# a210-4-band-eq.net
KiCad netlist of a schematic drawn in EAGLE
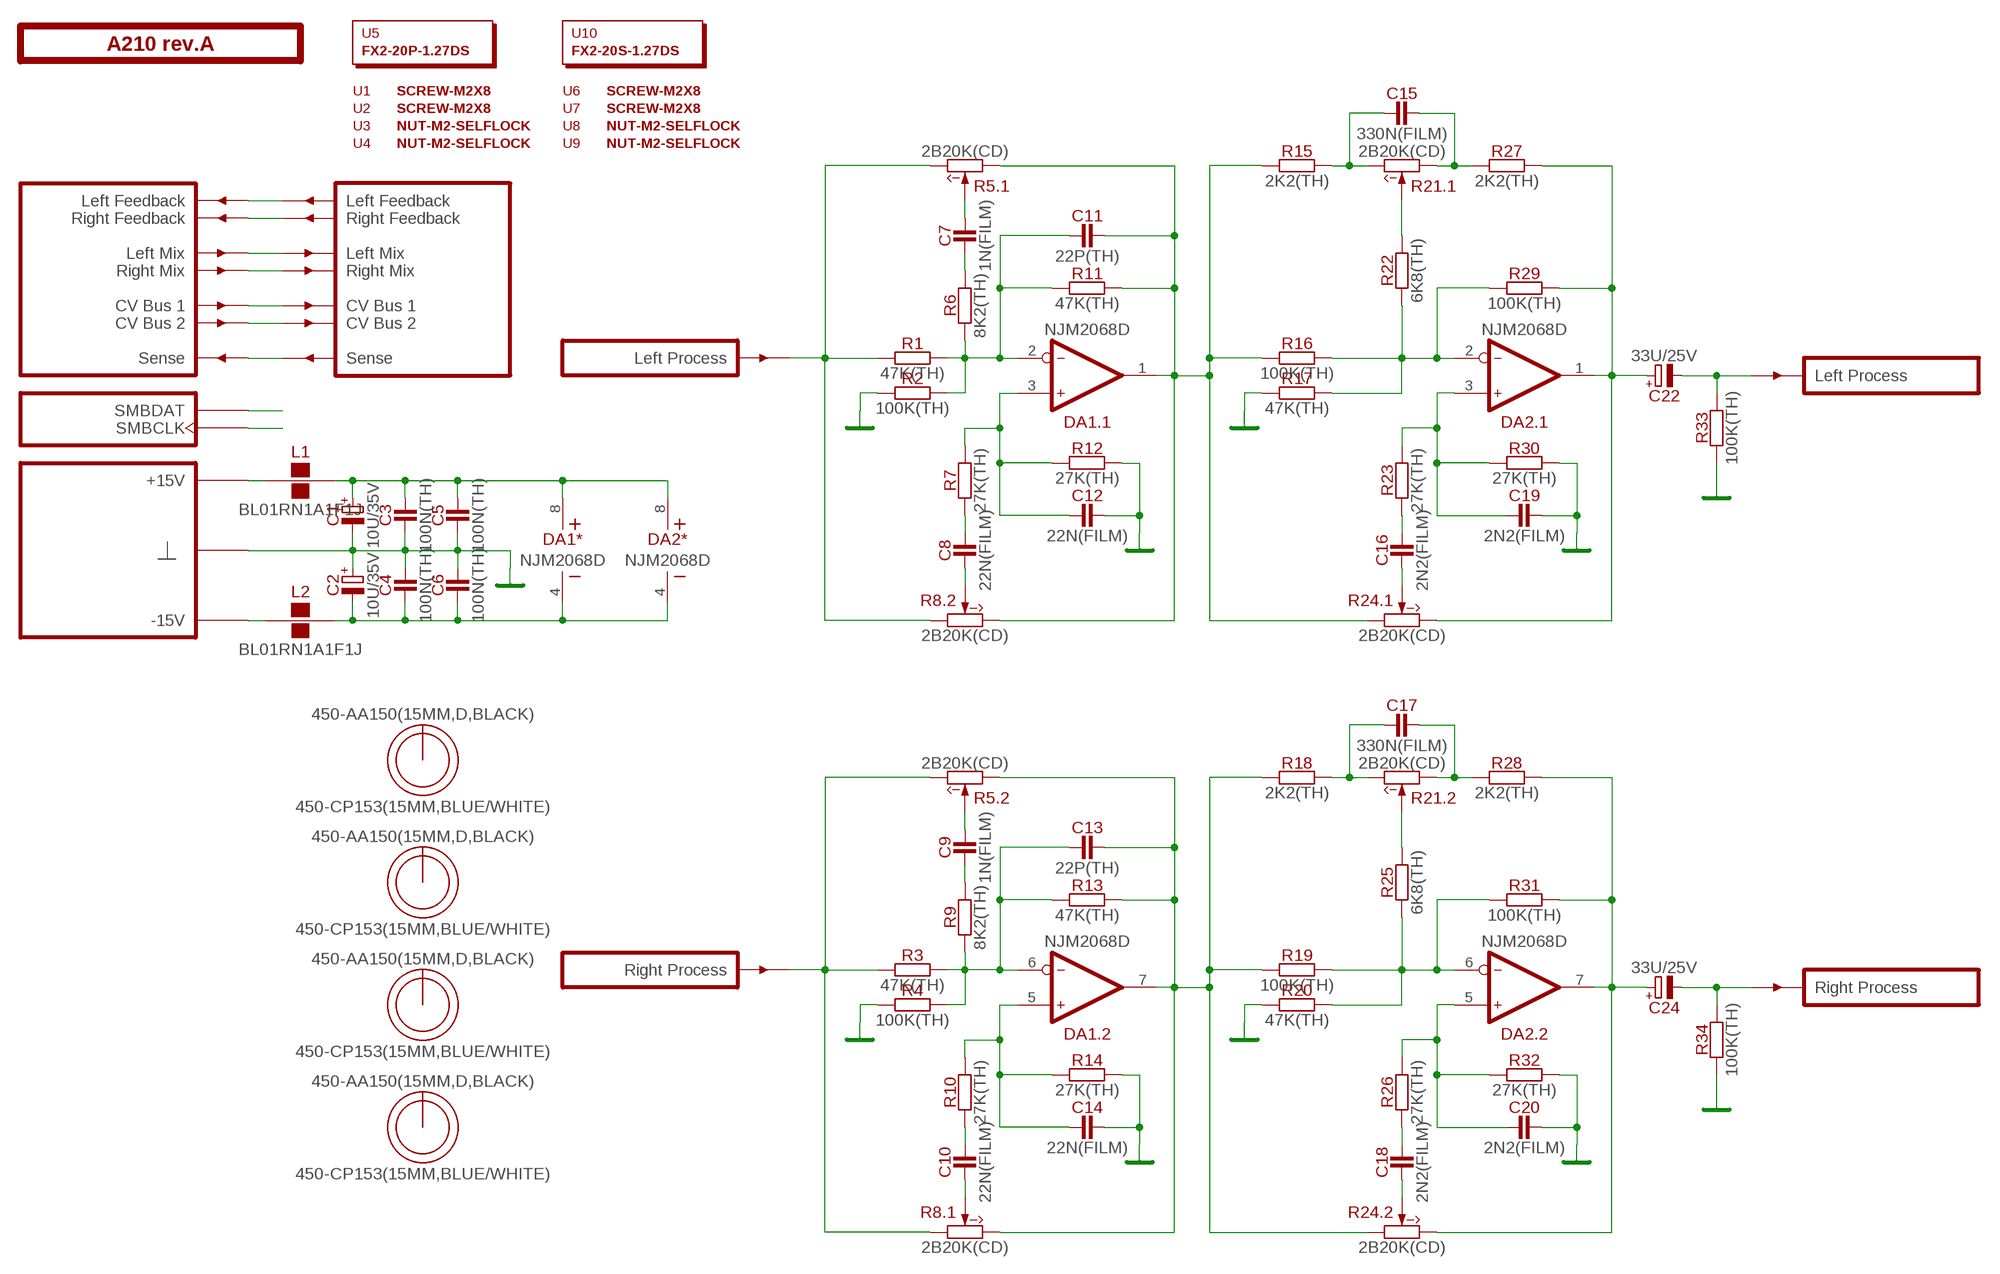
[diagram p0: schematic, sheet 1]

(export (version "E")
  (design (tool "Eeschema 10.0.6"))
  (components
    (comp (ref "C1")
      (value "10U/35V")
      (footprint "eagle-import:E2-5")
      (libsource (lib "eagle-import") (part "?10U/35V"))
    )
    (comp (ref "C2")
      (value "10U/35V")
      (footprint "eagle-import:E2-5")
      (libsource (lib "eagle-import") (part "?10U/35V"))
    )
    (comp (ref "C3")
      (value "100N(TH)")
      (footprint "eagle-import:C050-024X044")
      (libsource (lib "eagle-import") (part "?100N(TH)"))
    )
    (comp (ref "C4")
      (value "100N(TH)")
      (footprint "eagle-import:C050-024X044")
      (libsource (lib "eagle-import") (part "?100N(TH)"))
    )
    (comp (ref "C5")
      (value "100N(TH)")
      (footprint "eagle-import:C050-024X044")
      (libsource (lib "eagle-import") (part "?100N(TH)"))
    )
    (comp (ref "C6")
      (value "100N(TH)")
      (footprint "eagle-import:C050-024X044")
      (libsource (lib "eagle-import") (part "?100N(TH)"))
    )
    (comp (ref "C7")
      (value "1N(FILM)")
      (footprint "eagle-import:C050-025X075")
      (libsource (lib "eagle-import") (part "?1N(FILM)"))
    )
    (comp (ref "C8")
      (value "22N(FILM)")
      (footprint "eagle-import:C050-025X075")
      (libsource (lib "eagle-import") (part "?22N(FILM)"))
    )
    (comp (ref "C9")
      (value "1N(FILM)")
      (footprint "eagle-import:C050-025X075")
      (libsource (lib "eagle-import") (part "?1N(FILM)"))
    )
    (comp (ref "C10")
      (value "22N(FILM)")
      (footprint "eagle-import:C050-025X075")
      (libsource (lib "eagle-import") (part "?22N(FILM)"))
    )
    (comp (ref "C11")
      (value "22P(TH)")
      (footprint "eagle-import:C050-024X044")
      (libsource (lib "eagle-import") (part "?22P(TH)"))
    )
    (comp (ref "C12")
      (value "22N(FILM)")
      (footprint "eagle-import:C050-025X075")
      (libsource (lib "eagle-import") (part "?22N(FILM)"))
    )
    (comp (ref "C13")
      (value "22P(TH)")
      (footprint "eagle-import:C050-024X044")
      (libsource (lib "eagle-import") (part "?22P(TH)"))
    )
    (comp (ref "C14")
      (value "22N(FILM)")
      (footprint "eagle-import:C050-025X075")
      (libsource (lib "eagle-import") (part "?22N(FILM)"))
    )
    (comp (ref "C15")
      (value "330N(FILM)")
      (footprint "eagle-import:C050-035X075")
      (libsource (lib "eagle-import") (part "?330N(FILM)"))
    )
    (comp (ref "C16")
      (value "2N2(FILM)")
      (footprint "eagle-import:C050-025X075")
      (libsource (lib "eagle-import") (part "?2N2(FILM)"))
    )
    (comp (ref "C17")
      (value "330N(FILM)")
      (footprint "eagle-import:C050-035X075")
      (libsource (lib "eagle-import") (part "?330N(FILM)"))
    )
    (comp (ref "C18")
      (value "2N2(FILM)")
      (footprint "eagle-import:C050-025X075")
      (libsource (lib "eagle-import") (part "?2N2(FILM)"))
    )
    (comp (ref "C19")
      (value "2N2(FILM)")
      (footprint "eagle-import:C050-025X075")
      (libsource (lib "eagle-import") (part "?2N2(FILM)"))
    )
    (comp (ref "C20")
      (value "2N2(FILM)")
      (footprint "eagle-import:C050-025X075")
      (libsource (lib "eagle-import") (part "?2N2(FILM)"))
    )
    (comp (ref "C22")
      (value "33U/25V")
      (footprint "eagle-import:E2,5-7")
      (libsource (lib "eagle-import") (part "?33U/25V"))
    )
    (comp (ref "C24")
      (value "33U/25V")
      (footprint "eagle-import:E2,5-7")
      (libsource (lib "eagle-import") (part "?33U/25V"))
    )
    (comp (ref "DA1")
      (value "NJM2068D")
      (footprint "eagle-import:DIP-8")
      (libsource (lib "eagle-import") (part "NJM2068D"))
    )
    (comp (ref "DA2")
      (value "NJM2068D")
      (footprint "eagle-import:DIP-8")
      (libsource (lib "eagle-import") (part "NJM2068D"))
    )
    (comp (ref "L1")
      (value "BL01RN1A1F1J")
      (footprint "eagle-import:BL01RN1A")
      (libsource (lib "eagle-import") (part "BL01RN1A?1F1J"))
    )
    (comp (ref "L2")
      (value "BL01RN1A1F1J")
      (footprint "eagle-import:BL01RN1A")
      (libsource (lib "eagle-import") (part "BL01RN1A?1F1J"))
    )
    (comp (ref "O1")
      (value "450-AA150(15MM,D,BLACK)")
      (footprint "eagle-import:EMPTY")
      (libsource (lib "eagle-import") (part "450-AA?150(15MM,D,BLACK)"))
    )
    (comp (ref "O2")
      (value "450-AA150(15MM,D,BLACK)")
      (footprint "eagle-import:EMPTY")
      (libsource (lib "eagle-import") (part "450-AA?150(15MM,D,BLACK)"))
    )
    (comp (ref "O3")
      (value "450-AA150(15MM,D,BLACK)")
      (footprint "eagle-import:EMPTY")
      (libsource (lib "eagle-import") (part "450-AA?150(15MM,D,BLACK)"))
    )
    (comp (ref "O4")
      (value "450-AA150(15MM,D,BLACK)")
      (footprint "eagle-import:EMPTY")
      (libsource (lib "eagle-import") (part "450-AA?150(15MM,D,BLACK)"))
    )
    (comp (ref "O5")
      (value "450-CP153(15MM,BLUE/WHITE)")
      (footprint "eagle-import:EMPTY")
      (libsource (lib "eagle-import") (part "450-C?P153(15MM,BLUE/WHITE)"))
    )
    (comp (ref "O6")
      (value "450-CP153(15MM,BLUE/WHITE)")
      (footprint "eagle-import:EMPTY")
      (libsource (lib "eagle-import") (part "450-C?P153(15MM,BLUE/WHITE)"))
    )
    (comp (ref "O7")
      (value "450-CP153(15MM,BLUE/WHITE)")
      (footprint "eagle-import:EMPTY")
      (libsource (lib "eagle-import") (part "450-C?P153(15MM,BLUE/WHITE)"))
    )
    (comp (ref "O8")
      (value "450-CP153(15MM,BLUE/WHITE)")
      (footprint "eagle-import:EMPTY")
      (libsource (lib "eagle-import") (part "450-C?P153(15MM,BLUE/WHITE)"))
    )
    (comp (ref "PCB1")
      (value "A210 rev.A")
      (footprint "eagle-import:ST2-BOARD-50")
      (libsource (lib "eagle-import") (part "ST2-BOARD-?50"))
    )
    (comp (ref "R1")
      (value "47K(TH)")
      (footprint "eagle-import:R-0207_10")
      (libsource (lib "eagle-import") (part "?47K(TH)"))
    )
    (comp (ref "R2")
      (value "100K(TH)")
      (footprint "eagle-import:R-0207_10")
      (libsource (lib "eagle-import") (part "?100K(TH)"))
    )
    (comp (ref "R3")
      (value "47K(TH)")
      (footprint "eagle-import:R-0207_10")
      (libsource (lib "eagle-import") (part "?47K(TH)"))
    )
    (comp (ref "R4")
      (value "100K(TH)")
      (footprint "eagle-import:R-0207_10")
      (libsource (lib "eagle-import") (part "?100K(TH)"))
    )
    (comp (ref "R5")
      (value "2B20K(CD)")
      (footprint "eagle-import:RV11-DUAL")
      (libsource (lib "eagle-import") (part "2?B20K(CD)"))
    )
    (comp (ref "R6")
      (value "8K2(TH)")
      (footprint "eagle-import:R-0207_10")
      (libsource (lib "eagle-import") (part "?8K2(TH)"))
    )
    (comp (ref "R7")
      (value "27K(TH)")
      (footprint "eagle-import:R-0207_10")
      (libsource (lib "eagle-import") (part "?27K(TH)"))
    )
    (comp (ref "R8")
      (value "2B20K(CD)")
      (footprint "eagle-import:RV11-DUAL")
      (libsource (lib "eagle-import") (part "2?B20K(CD)"))
    )
    (comp (ref "R9")
      (value "8K2(TH)")
      (footprint "eagle-import:R-0207_10")
      (libsource (lib "eagle-import") (part "?8K2(TH)"))
    )
    (comp (ref "R10")
      (value "27K(TH)")
      (footprint "eagle-import:R-0207_10")
      (libsource (lib "eagle-import") (part "?27K(TH)"))
    )
    (comp (ref "R11")
      (value "47K(TH)")
      (footprint "eagle-import:R-0207_10")
      (libsource (lib "eagle-import") (part "?47K(TH)"))
    )
    (comp (ref "R12")
      (value "27K(TH)")
      (footprint "eagle-import:R-0207_10")
      (libsource (lib "eagle-import") (part "?27K(TH)"))
    )
    (comp (ref "R13")
      (value "47K(TH)")
      (footprint "eagle-import:R-0207_10")
      (libsource (lib "eagle-import") (part "?47K(TH)"))
    )
    (comp (ref "R14")
      (value "27K(TH)")
      (footprint "eagle-import:R-0207_10")
      (libsource (lib "eagle-import") (part "?27K(TH)"))
    )
    (comp (ref "R15")
      (value "2K2(TH)")
      (footprint "eagle-import:R-0207_10")
      (libsource (lib "eagle-import") (part "?2K2(TH)"))
    )
    (comp (ref "R16")
      (value "100K(TH)")
      (footprint "eagle-import:R-0207_10")
      (libsource (lib "eagle-import") (part "?100K(TH)"))
    )
    (comp (ref "R17")
      (value "47K(TH)")
      (footprint "eagle-import:R-0207_10")
      (libsource (lib "eagle-import") (part "?47K(TH)"))
    )
    (comp (ref "R18")
      (value "2K2(TH)")
      (footprint "eagle-import:R-0207_10")
      (libsource (lib "eagle-import") (part "?2K2(TH)"))
    )
    (comp (ref "R19")
      (value "100K(TH)")
      (footprint "eagle-import:R-0207_10")
      (libsource (lib "eagle-import") (part "?100K(TH)"))
    )
    (comp (ref "R20")
      (value "47K(TH)")
      (footprint "eagle-import:R-0207_10")
      (libsource (lib "eagle-import") (part "?47K(TH)"))
    )
    (comp (ref "R21")
      (value "2B20K(CD)")
      (footprint "eagle-import:RV11-DUAL")
      (libsource (lib "eagle-import") (part "2?B20K(CD)"))
    )
    (comp (ref "R22")
      (value "6K8(TH)")
      (footprint "eagle-import:R-0207_10")
      (libsource (lib "eagle-import") (part "?6K8(TH)"))
    )
    (comp (ref "R23")
      (value "27K(TH)")
      (footprint "eagle-import:R-0207_10")
      (libsource (lib "eagle-import") (part "?27K(TH)"))
    )
    (comp (ref "R24")
      (value "2B20K(CD)")
      (footprint "eagle-import:RV11-DUAL")
      (libsource (lib "eagle-import") (part "2?B20K(CD)"))
    )
    (comp (ref "R25")
      (value "6K8(TH)")
      (footprint "eagle-import:R-0207_10")
      (libsource (lib "eagle-import") (part "?6K8(TH)"))
    )
    (comp (ref "R26")
      (value "27K(TH)")
      (footprint "eagle-import:R-0207_10")
      (libsource (lib "eagle-import") (part "?27K(TH)"))
    )
    (comp (ref "R27")
      (value "2K2(TH)")
      (footprint "eagle-import:R-0207_10")
      (libsource (lib "eagle-import") (part "?2K2(TH)"))
    )
    (comp (ref "R28")
      (value "2K2(TH)")
      (footprint "eagle-import:R-0207_10")
      (libsource (lib "eagle-import") (part "?2K2(TH)"))
    )
    (comp (ref "R29")
      (value "100K(TH)")
      (footprint "eagle-import:R-0207_10")
      (libsource (lib "eagle-import") (part "?100K(TH)"))
    )
    (comp (ref "R30")
      (value "27K(TH)")
      (footprint "eagle-import:R-0207_10")
      (libsource (lib "eagle-import") (part "?27K(TH)"))
    )
    (comp (ref "R31")
      (value "100K(TH)")
      (footprint "eagle-import:R-0207_10")
      (libsource (lib "eagle-import") (part "?100K(TH)"))
    )
    (comp (ref "R32")
      (value "27K(TH)")
      (footprint "eagle-import:R-0207_10")
      (libsource (lib "eagle-import") (part "?27K(TH)"))
    )
    (comp (ref "R33")
      (value "100K(TH)")
      (footprint "eagle-import:R-0207_10")
      (libsource (lib "eagle-import") (part "?100K(TH)"))
    )
    (comp (ref "R34")
      (value "100K(TH)")
      (footprint "eagle-import:R-0207_10")
      (libsource (lib "eagle-import") (part "?100K(TH)"))
    )
    (comp (ref "U1")
      (value "SCREW-M2X8")
      (footprint "eagle-import:EMPTY")
      (libsource (lib "eagle-import") (part "?SCREW-M2X8"))
    )
    (comp (ref "U2")
      (value "SCREW-M2X8")
      (footprint "eagle-import:EMPTY")
      (libsource (lib "eagle-import") (part "?SCREW-M2X8"))
    )
    (comp (ref "U3")
      (value "NUT-M2-SELFLOCK")
      (footprint "eagle-import:EMPTY")
      (libsource (lib "eagle-import") (part "?NUT-M2-SELFLOCK"))
    )
    (comp (ref "U4")
      (value "NUT-M2-SELFLOCK")
      (footprint "eagle-import:EMPTY")
      (libsource (lib "eagle-import") (part "?NUT-M2-SELFLOCK"))
    )
    (comp (ref "U5")
      (value "FX2-20P-1.27DS")
      (footprint "eagle-import:EMPTY")
      (libsource (lib "eagle-import") (part "?FX2-20P-1.27DS"))
    )
    (comp (ref "U6")
      (value "SCREW-M2X8")
      (footprint "eagle-import:EMPTY")
      (libsource (lib "eagle-import") (part "?SCREW-M2X8"))
    )
    (comp (ref "U7")
      (value "SCREW-M2X8")
      (footprint "eagle-import:EMPTY")
      (libsource (lib "eagle-import") (part "?SCREW-M2X8"))
    )
    (comp (ref "U8")
      (value "NUT-M2-SELFLOCK")
      (footprint "eagle-import:EMPTY")
      (libsource (lib "eagle-import") (part "?NUT-M2-SELFLOCK"))
    )
    (comp (ref "U9")
      (value "NUT-M2-SELFLOCK")
      (footprint "eagle-import:EMPTY")
      (libsource (lib "eagle-import") (part "?NUT-M2-SELFLOCK"))
    )
    (comp (ref "U10")
      (value "FX2-20S-1.27DS")
      (footprint "eagle-import:EMPTY")
      (libsource (lib "eagle-import") (part "?FX2-20S-1.27DS"))
    )
  )
  (nets
    (net (code "1") (name "GND") (class "Default")
      (node (ref "C1") (pin "-") (pinfunction "-_-") (pintype "passive"))
      (node (ref "C12") (pin "2") (pinfunction "2_2") (pintype "passive"))
      (node (ref "C14") (pin "2") (pinfunction "2_2") (pintype "passive"))
      (node (ref "C19") (pin "2") (pinfunction "2_2") (pintype "passive"))
      (node (ref "C2") (pin "+") (pinfunction "+_+") (pintype "passive"))
      (node (ref "C20") (pin "2") (pinfunction "2_2") (pintype "passive"))
      (node (ref "C3") (pin "1") (pinfunction "1_1") (pintype "passive"))
      (node (ref "C4") (pin "2") (pinfunction "2_2") (pintype "passive"))
      (node (ref "C5") (pin "1") (pinfunction "1_1") (pintype "passive"))
      (node (ref "C6") (pin "2") (pinfunction "2_2") (pintype "passive"))
      (node (ref "PCB1") (pin "B4") (pinfunction "GND_B4") (pintype "bidirectional"))
      (node (ref "PCB1") (pin "B4'") (pinfunction "GND_B4'") (pintype "bidirectional"))
      (node (ref "PCB1") (pin "B5") (pinfunction "GND_B5") (pintype "bidirectional"))
      (node (ref "PCB1") (pin "B5'") (pinfunction "GND_B5'") (pintype "bidirectional"))
      (node (ref "PCB1") (pin "B6") (pinfunction "GND_B6") (pintype "bidirectional"))
      (node (ref "PCB1") (pin "B6'") (pinfunction "GND_B6'") (pintype "bidirectional"))
      (node (ref "PCB1") (pin "B7") (pinfunction "GND_B7") (pintype "bidirectional"))
      (node (ref "PCB1") (pin "B7'") (pinfunction "GND_B7'") (pintype "bidirectional"))
      (node (ref "PCB1") (pin "B8") (pinfunction "GND_B8") (pintype "bidirectional"))
      (node (ref "PCB1") (pin "B8'") (pinfunction "GND_B8'") (pintype "bidirectional"))
      (node (ref "R12") (pin "2") (pinfunction "2_2") (pintype "passive"))
      (node (ref "R14") (pin "2") (pinfunction "2_2") (pintype "passive"))
      (node (ref "R17") (pin "1") (pinfunction "1_1") (pintype "passive"))
      (node (ref "R2") (pin "1") (pinfunction "1_1") (pintype "passive"))
      (node (ref "R20") (pin "1") (pinfunction "1_1") (pintype "passive"))
      (node (ref "R30") (pin "2") (pinfunction "2_2") (pintype "passive"))
      (node (ref "R32") (pin "2") (pinfunction "2_2") (pintype "passive"))
      (node (ref "R33") (pin "1") (pinfunction "1_1") (pintype "passive"))
      (node (ref "R34") (pin "1") (pinfunction "1_1") (pintype "passive"))
      (node (ref "R4") (pin "1") (pinfunction "1_1") (pintype "passive"))
    )
    (net (code "2") (name "Net-(C7-Pad1)") (class "Default")
      (node (ref "C7") (pin "1") (pinfunction "1_1") (pintype "passive"))
      (node (ref "R6") (pin "2") (pinfunction "2_2") (pintype "passive"))
    )
    (net (code "3") (name "Net-(C8-Pad2)") (class "Default")
      (node (ref "C8") (pin "2") (pinfunction "2_2") (pintype "passive"))
      (node (ref "R7") (pin "1") (pinfunction "1_1") (pintype "passive"))
    )
    (net (code "4") (name "Net-(C9-Pad1)") (class "Default")
      (node (ref "C9") (pin "1") (pinfunction "1_1") (pintype "passive"))
      (node (ref "R9") (pin "2") (pinfunction "2_2") (pintype "passive"))
    )
    (net (code "5") (name "Net-(C10-Pad2)") (class "Default")
      (node (ref "C10") (pin "2") (pinfunction "2_2") (pintype "passive"))
      (node (ref "R10") (pin "1") (pinfunction "1_1") (pintype "passive"))
    )
    (net (code "6") (name "Net-(C16-Pad2)") (class "Default")
      (node (ref "C16") (pin "2") (pinfunction "2_2") (pintype "passive"))
      (node (ref "R23") (pin "1") (pinfunction "1_1") (pintype "passive"))
    )
    (net (code "7") (name "Net-(C18-Pad2)") (class "Default")
      (node (ref "C18") (pin "2") (pinfunction "2_2") (pintype "passive"))
      (node (ref "R26") (pin "1") (pinfunction "1_1") (pintype "passive"))
    )
    (net (code "8") (name "Net-(DA1A-V+)") (class "Default")
      (node (ref "C1") (pin "+") (pinfunction "+_+") (pintype "passive"))
      (node (ref "C3") (pin "2") (pinfunction "2_2") (pintype "passive"))
      (node (ref "C5") (pin "2") (pinfunction "2_2") (pintype "passive"))
      (node (ref "DA1") (pin "8") (pinfunction "V+_8") (pintype "power_in"))
      (node (ref "DA2") (pin "8") (pinfunction "V+_8") (pintype "power_in"))
      (node (ref "L1") (pin "2") (pinfunction "2_2") (pintype "passive"))
    )
    (net (code "9") (name "Net-(DA1A-V-)") (class "Default")
      (node (ref "C2") (pin "-") (pinfunction "-_-") (pintype "passive"))
      (node (ref "C4") (pin "1") (pinfunction "1_1") (pintype "passive"))
      (node (ref "C6") (pin "1") (pinfunction "1_1") (pintype "passive"))
      (node (ref "DA1") (pin "4") (pinfunction "V-_4") (pintype "power_in"))
      (node (ref "DA2") (pin "4") (pinfunction "V-_4") (pintype "power_in"))
      (node (ref "L2") (pin "2") (pinfunction "2_2") (pintype "passive"))
    )
    (net (code "10") (name "Net-(DA1B-IN+)") (class "Default")
      (node (ref "C12") (pin "1") (pinfunction "1_1") (pintype "passive"))
      (node (ref "DA1") (pin "3") (pinfunction "IN+_3") (pintype "input"))
      (node (ref "R12") (pin "1") (pinfunction "1_1") (pintype "passive"))
      (node (ref "R7") (pin "2") (pinfunction "2_2") (pintype "passive"))
    )
    (net (code "11") (name "Net-(DA1B-IN-)") (class "Default")
      (node (ref "C11") (pin "1") (pinfunction "1_1") (pintype "passive"))
      (node (ref "DA1") (pin "2") (pinfunction "IN-_2") (pintype "input"))
      (node (ref "R1") (pin "2") (pinfunction "2_2") (pintype "passive"))
      (node (ref "R11") (pin "1") (pinfunction "1_1") (pintype "passive"))
      (node (ref "R2") (pin "2") (pinfunction "2_2") (pintype "passive"))
      (node (ref "R6") (pin "1") (pinfunction "1_1") (pintype "passive"))
    )
    (net (code "12") (name "Net-(DA1B-OUT)") (class "Default")
      (node (ref "C11") (pin "2") (pinfunction "2_2") (pintype "passive"))
      (node (ref "DA1") (pin "1") (pinfunction "OUT_1") (pintype "output"))
      (node (ref "R11") (pin "2") (pinfunction "2_2") (pintype "passive"))
      (node (ref "R15") (pin "1") (pinfunction "1_1") (pintype "passive"))
      (node (ref "R16") (pin "1") (pinfunction "1_1") (pintype "passive"))
      (node (ref "R24") (pin "1") (pinfunction "CCW_1") (pintype "passive"))
      (node (ref "R5") (pin "1") (pinfunction "CCW_1") (pintype "passive"))
      (node (ref "R8") (pin "3'") (pinfunction "CW_3'") (pintype "passive"))
    )
    (net (code "13") (name "Net-(DA1C-IN+)") (class "Default")
      (node (ref "C14") (pin "1") (pinfunction "1_1") (pintype "passive"))
      (node (ref "DA1") (pin "5") (pinfunction "IN+_5") (pintype "input"))
      (node (ref "R10") (pin "2") (pinfunction "2_2") (pintype "passive"))
      (node (ref "R14") (pin "1") (pinfunction "1_1") (pintype "passive"))
    )
    (net (code "14") (name "Net-(DA1C-IN-)") (class "Default")
      (node (ref "C13") (pin "1") (pinfunction "1_1") (pintype "passive"))
      (node (ref "DA1") (pin "6") (pinfunction "IN-_6") (pintype "input"))
      (node (ref "R13") (pin "1") (pinfunction "1_1") (pintype "passive"))
      (node (ref "R3") (pin "2") (pinfunction "2_2") (pintype "passive"))
      (node (ref "R4") (pin "2") (pinfunction "2_2") (pintype "passive"))
      (node (ref "R9") (pin "1") (pinfunction "1_1") (pintype "passive"))
    )
    (net (code "15") (name "Net-(DA1C-OUT)") (class "Default")
      (node (ref "C13") (pin "2") (pinfunction "2_2") (pintype "passive"))
      (node (ref "DA1") (pin "7") (pinfunction "OUT_7") (pintype "output"))
      (node (ref "R13") (pin "2") (pinfunction "2_2") (pintype "passive"))
      (node (ref "R18") (pin "1") (pinfunction "1_1") (pintype "passive"))
      (node (ref "R19") (pin "1") (pinfunction "1_1") (pintype "passive"))
      (node (ref "R24") (pin "1'") (pinfunction "CCW_1'") (pintype "passive"))
      (node (ref "R5") (pin "1'") (pinfunction "CCW_1'") (pintype "passive"))
      (node (ref "R8") (pin "3") (pinfunction "CW_3") (pintype "passive"))
    )
    (net (code "16") (name "Net-(DA2B-IN+)") (class "Default")
      (node (ref "C19") (pin "1") (pinfunction "1_1") (pintype "passive"))
      (node (ref "DA2") (pin "3") (pinfunction "IN+_3") (pintype "input"))
      (node (ref "R23") (pin "2") (pinfunction "2_2") (pintype "passive"))
      (node (ref "R30") (pin "1") (pinfunction "1_1") (pintype "passive"))
    )
    (net (code "17") (name "Net-(DA2B-IN-)") (class "Default")
      (node (ref "DA2") (pin "2") (pinfunction "IN-_2") (pintype "input"))
      (node (ref "R16") (pin "2") (pinfunction "2_2") (pintype "passive"))
      (node (ref "R17") (pin "2") (pinfunction "2_2") (pintype "passive"))
      (node (ref "R22") (pin "1") (pinfunction "1_1") (pintype "passive"))
      (node (ref "R29") (pin "1") (pinfunction "1_1") (pintype "passive"))
    )
    (net (code "18") (name "Net-(DA2B-OUT)") (class "Default")
      (node (ref "C22") (pin "+") (pinfunction "+_+") (pintype "passive"))
      (node (ref "DA2") (pin "1") (pinfunction "OUT_1") (pintype "output"))
      (node (ref "R24") (pin "3") (pinfunction "CW_3") (pintype "passive"))
      (node (ref "R27") (pin "2") (pinfunction "2_2") (pintype "passive"))
      (node (ref "R29") (pin "2") (pinfunction "2_2") (pintype "passive"))
    )
    (net (code "19") (name "Net-(DA2C-IN+)") (class "Default")
      (node (ref "C20") (pin "1") (pinfunction "1_1") (pintype "passive"))
      (node (ref "DA2") (pin "5") (pinfunction "IN+_5") (pintype "input"))
      (node (ref "R26") (pin "2") (pinfunction "2_2") (pintype "passive"))
      (node (ref "R32") (pin "1") (pinfunction "1_1") (pintype "passive"))
    )
    (net (code "20") (name "Net-(DA2C-IN-)") (class "Default")
      (node (ref "DA2") (pin "6") (pinfunction "IN-_6") (pintype "input"))
      (node (ref "R19") (pin "2") (pinfunction "2_2") (pintype "passive"))
      (node (ref "R20") (pin "2") (pinfunction "2_2") (pintype "passive"))
      (node (ref "R25") (pin "1") (pinfunction "1_1") (pintype "passive"))
      (node (ref "R31") (pin "1") (pinfunction "1_1") (pintype "passive"))
    )
    (net (code "21") (name "Net-(DA2C-OUT)") (class "Default")
      (node (ref "C24") (pin "+") (pinfunction "+_+") (pintype "passive"))
      (node (ref "DA2") (pin "7") (pinfunction "OUT_7") (pintype "output"))
      (node (ref "R24") (pin "3'") (pinfunction "CW_3'") (pintype "passive"))
      (node (ref "R28") (pin "2") (pinfunction "2_2") (pintype "passive"))
      (node (ref "R31") (pin "2") (pinfunction "2_2") (pintype "passive"))
    )
    (net (code "22") (name "Net-(L1-Pad1)") (class "Default")
      (node (ref "L1") (pin "1") (pinfunction "1_1") (pintype "passive"))
      (node (ref "PCB1") (pin "A+15") (pinfunction "P+15V_A+15") (pintype "bidirectional"))
      (node (ref "PCB1") (pin "A+15'") (pinfunction "P+15V_A+15'") (pintype "bidirectional"))
      (node (ref "PCB1") (pin "B+15") (pinfunction "P+15V_B+15") (pintype "bidirectional"))
      (node (ref "PCB1") (pin "B+15'") (pinfunction "P+15V_B+15'") (pintype "bidirectional"))
    )
    (net (code "23") (name "Net-(L2-Pad1)") (class "Default")
      (node (ref "L2") (pin "1") (pinfunction "1_1") (pintype "passive"))
      (node (ref "PCB1") (pin "A-15") (pinfunction "P-15V_A-15") (pintype "bidirectional"))
      (node (ref "PCB1") (pin "A-15'") (pinfunction "P-15V_A-15'") (pintype "bidirectional"))
      (node (ref "PCB1") (pin "B-15") (pinfunction "P-15V_B-15") (pintype "bidirectional"))
      (node (ref "PCB1") (pin "B-15'") (pinfunction "P-15V_B-15'") (pintype "bidirectional"))
    )
    (net (code "24") (name "Net-(PCB1B-INL)") (class "Default")
      (node (ref "PCB1") (pin "BINL") (pinfunction "INL_BINL") (pintype "bidirectional"))
      (node (ref "R1") (pin "1") (pinfunction "1_1") (pintype "passive"))
      (node (ref "R5") (pin "3") (pinfunction "CW_3") (pintype "passive"))
      (node (ref "R8") (pin "1'") (pinfunction "CCW_1'") (pintype "passive"))
    )
    (net (code "25") (name "Net-(PCB1C-INR)") (class "Default")
      (node (ref "PCB1") (pin "BINR") (pinfunction "INR_BINR") (pintype "bidirectional"))
      (node (ref "R3") (pin "1") (pinfunction "1_1") (pintype "passive"))
      (node (ref "R5") (pin "3'") (pinfunction "CW_3'") (pintype "passive"))
      (node (ref "R8") (pin "1") (pinfunction "CCW_1") (pintype "passive"))
    )
    (net (code "26") (name "Net-(PCB1D-OUTL)") (class "Default")
      (node (ref "C22") (pin "-") (pinfunction "-_-") (pintype "passive"))
      (node (ref "PCB1") (pin "BOUTL'") (pinfunction "OUTL_BOUTL'") (pintype "bidirectional"))
      (node (ref "R33") (pin "2") (pinfunction "2_2") (pintype "passive"))
    )
    (net (code "27") (name "Net-(PCB1E-OUTR)") (class "Default")
      (node (ref "C24") (pin "-") (pinfunction "-_-") (pintype "passive"))
      (node (ref "PCB1") (pin "BOUTR'") (pinfunction "OUTR_BOUTR'") (pintype "bidirectional"))
      (node (ref "R34") (pin "2") (pinfunction "2_2") (pintype "passive"))
    )
    (net (code "28") (name "Net-(PCB1F-CV1)") (class "Default")
      (node (ref "PCB1") (pin "ACV1") (pinfunction "CV1_ACV1") (pintype "bidirectional"))
      (node (ref "PCB1") (pin "ACV1'") (pinfunction "CV1'_ACV1'") (pintype "bidirectional"))
    )
    (net (code "29") (name "Net-(PCB1F-CV2)") (class "Default")
      (node (ref "PCB1") (pin "ACV2") (pinfunction "CV2_ACV2") (pintype "bidirectional"))
      (node (ref "PCB1") (pin "ACV2'") (pinfunction "CV2'_ACV2'") (pintype "bidirectional"))
    )
    (net (code "30") (name "Net-(PCB1F-LFBK)") (class "Default")
      (node (ref "PCB1") (pin "ALFBK") (pinfunction "LFBK_ALFBK") (pintype "bidirectional"))
      (node (ref "PCB1") (pin "ALFBK'") (pinfunction "LFBK'_ALFBK'") (pintype "bidirectional"))
    )
    (net (code "31") (name "Net-(PCB1F-LMIX)") (class "Default")
      (node (ref "PCB1") (pin "ALMIX") (pinfunction "LMIX_ALMIX") (pintype "bidirectional"))
      (node (ref "PCB1") (pin "ALMIX'") (pinfunction "LMIX'_ALMIX'") (pintype "bidirectional"))
    )
    (net (code "32") (name "Net-(PCB1F-RFBK)") (class "Default")
      (node (ref "PCB1") (pin "ARFBK") (pinfunction "RFBK_ARFBK") (pintype "bidirectional"))
      (node (ref "PCB1") (pin "ARFBK'") (pinfunction "RFBK'_ARFBK'") (pintype "bidirectional"))
    )
    (net (code "33") (name "Net-(PCB1F-RMIX)") (class "Default")
      (node (ref "PCB1") (pin "ARMIX") (pinfunction "RMIX_ARMIX") (pintype "bidirectional"))
      (node (ref "PCB1") (pin "ARMIX'") (pinfunction "RMIX'_ARMIX'") (pintype "bidirectional"))
    )
    (net (code "34") (name "Net-(PCB1F-SENSE)") (class "Default")
      (node (ref "PCB1") (pin "BSENSE") (pinfunction "SENSE_BSENSE") (pintype "bidirectional"))
      (node (ref "PCB1") (pin "BSENSE'") (pinfunction "SENSE'_BSENSE'") (pintype "bidirectional"))
    )
    (net (code "35") (name "Net-(PCB1H-SMBCLK-PadASMBCLK')") (class "Default")
      (node (ref "PCB1") (pin "ASMBCLK") (pinfunction "SMBCLK_ASMBCLK") (pintype "bidirectional"))
      (node (ref "PCB1") (pin "ASMBCLK'") (pinfunction "SMBCLK_ASMBCLK'") (pintype "bidirectional"))
    )
    (net (code "36") (name "Net-(PCB1H-SMBDAT-PadASMBDAT')") (class "Default")
      (node (ref "PCB1") (pin "ASMBDAT") (pinfunction "SMBDAT_ASMBDAT") (pintype "bidirectional"))
      (node (ref "PCB1") (pin "ASMBDAT'") (pinfunction "SMBDAT_ASMBDAT'") (pintype "bidirectional"))
    )
    (net (code "37") (name "Net-(R5A-W)") (class "Default")
      (node (ref "C7") (pin "2") (pinfunction "2_2") (pintype "passive"))
      (node (ref "R5") (pin "2") (pinfunction "W_2") (pintype "passive"))
    )
    (net (code "38") (name "Net-(R5B-W)") (class "Default")
      (node (ref "C9") (pin "2") (pinfunction "2_2") (pintype "passive"))
      (node (ref "R5") (pin "2'") (pinfunction "W_2'") (pintype "passive"))
    )
    (net (code "39") (name "Net-(R8A-W)") (class "Default")
      (node (ref "C10") (pin "1") (pinfunction "1_1") (pintype "passive"))
      (node (ref "R8") (pin "2") (pinfunction "W_2") (pintype "passive"))
    )
    (net (code "40") (name "Net-(R8B-W)") (class "Default")
      (node (ref "C8") (pin "1") (pinfunction "1_1") (pintype "passive"))
      (node (ref "R8") (pin "2'") (pinfunction "W_2'") (pintype "passive"))
    )
    (net (code "41") (name "Net-(R21A-CCW)") (class "Default")
      (node (ref "C15") (pin "2") (pinfunction "2_2") (pintype "passive"))
      (node (ref "R21") (pin "1") (pinfunction "CCW_1") (pintype "passive"))
      (node (ref "R27") (pin "1") (pinfunction "1_1") (pintype "passive"))
    )
    (net (code "42") (name "Net-(R21A-CW)") (class "Default")
      (node (ref "C15") (pin "1") (pinfunction "1_1") (pintype "passive"))
      (node (ref "R15") (pin "2") (pinfunction "2_2") (pintype "passive"))
      (node (ref "R21") (pin "3") (pinfunction "CW_3") (pintype "passive"))
    )
    (net (code "43") (name "Net-(R21A-W)") (class "Default")
      (node (ref "R21") (pin "2") (pinfunction "W_2") (pintype "passive"))
      (node (ref "R22") (pin "2") (pinfunction "2_2") (pintype "passive"))
    )
    (net (code "44") (name "Net-(R21B-CCW)") (class "Default")
      (node (ref "C17") (pin "2") (pinfunction "2_2") (pintype "passive"))
      (node (ref "R21") (pin "1'") (pinfunction "CCW_1'") (pintype "passive"))
      (node (ref "R28") (pin "1") (pinfunction "1_1") (pintype "passive"))
    )
    (net (code "45") (name "Net-(R21B-CW)") (class "Default")
      (node (ref "C17") (pin "1") (pinfunction "1_1") (pintype "passive"))
      (node (ref "R18") (pin "2") (pinfunction "2_2") (pintype "passive"))
      (node (ref "R21") (pin "3'") (pinfunction "CW_3'") (pintype "passive"))
    )
    (net (code "46") (name "Net-(R21B-W)") (class "Default")
      (node (ref "R21") (pin "2'") (pinfunction "W_2'") (pintype "passive"))
      (node (ref "R25") (pin "2") (pinfunction "2_2") (pintype "passive"))
    )
    (net (code "47") (name "Net-(R24A-W)") (class "Default")
      (node (ref "C16") (pin "1") (pinfunction "1_1") (pintype "passive"))
      (node (ref "R24") (pin "2") (pinfunction "W_2") (pintype "passive"))
    )
    (net (code "48") (name "Net-(R24B-W)") (class "Default")
      (node (ref "C18") (pin "1") (pinfunction "1_1") (pintype "passive"))
      (node (ref "R24") (pin "2'") (pinfunction "W_2'") (pintype "passive"))
    )
  )
)
